# Schematic-DeepAmbiente.net
KiCad netlist of a schematic drawn in Altium Designer
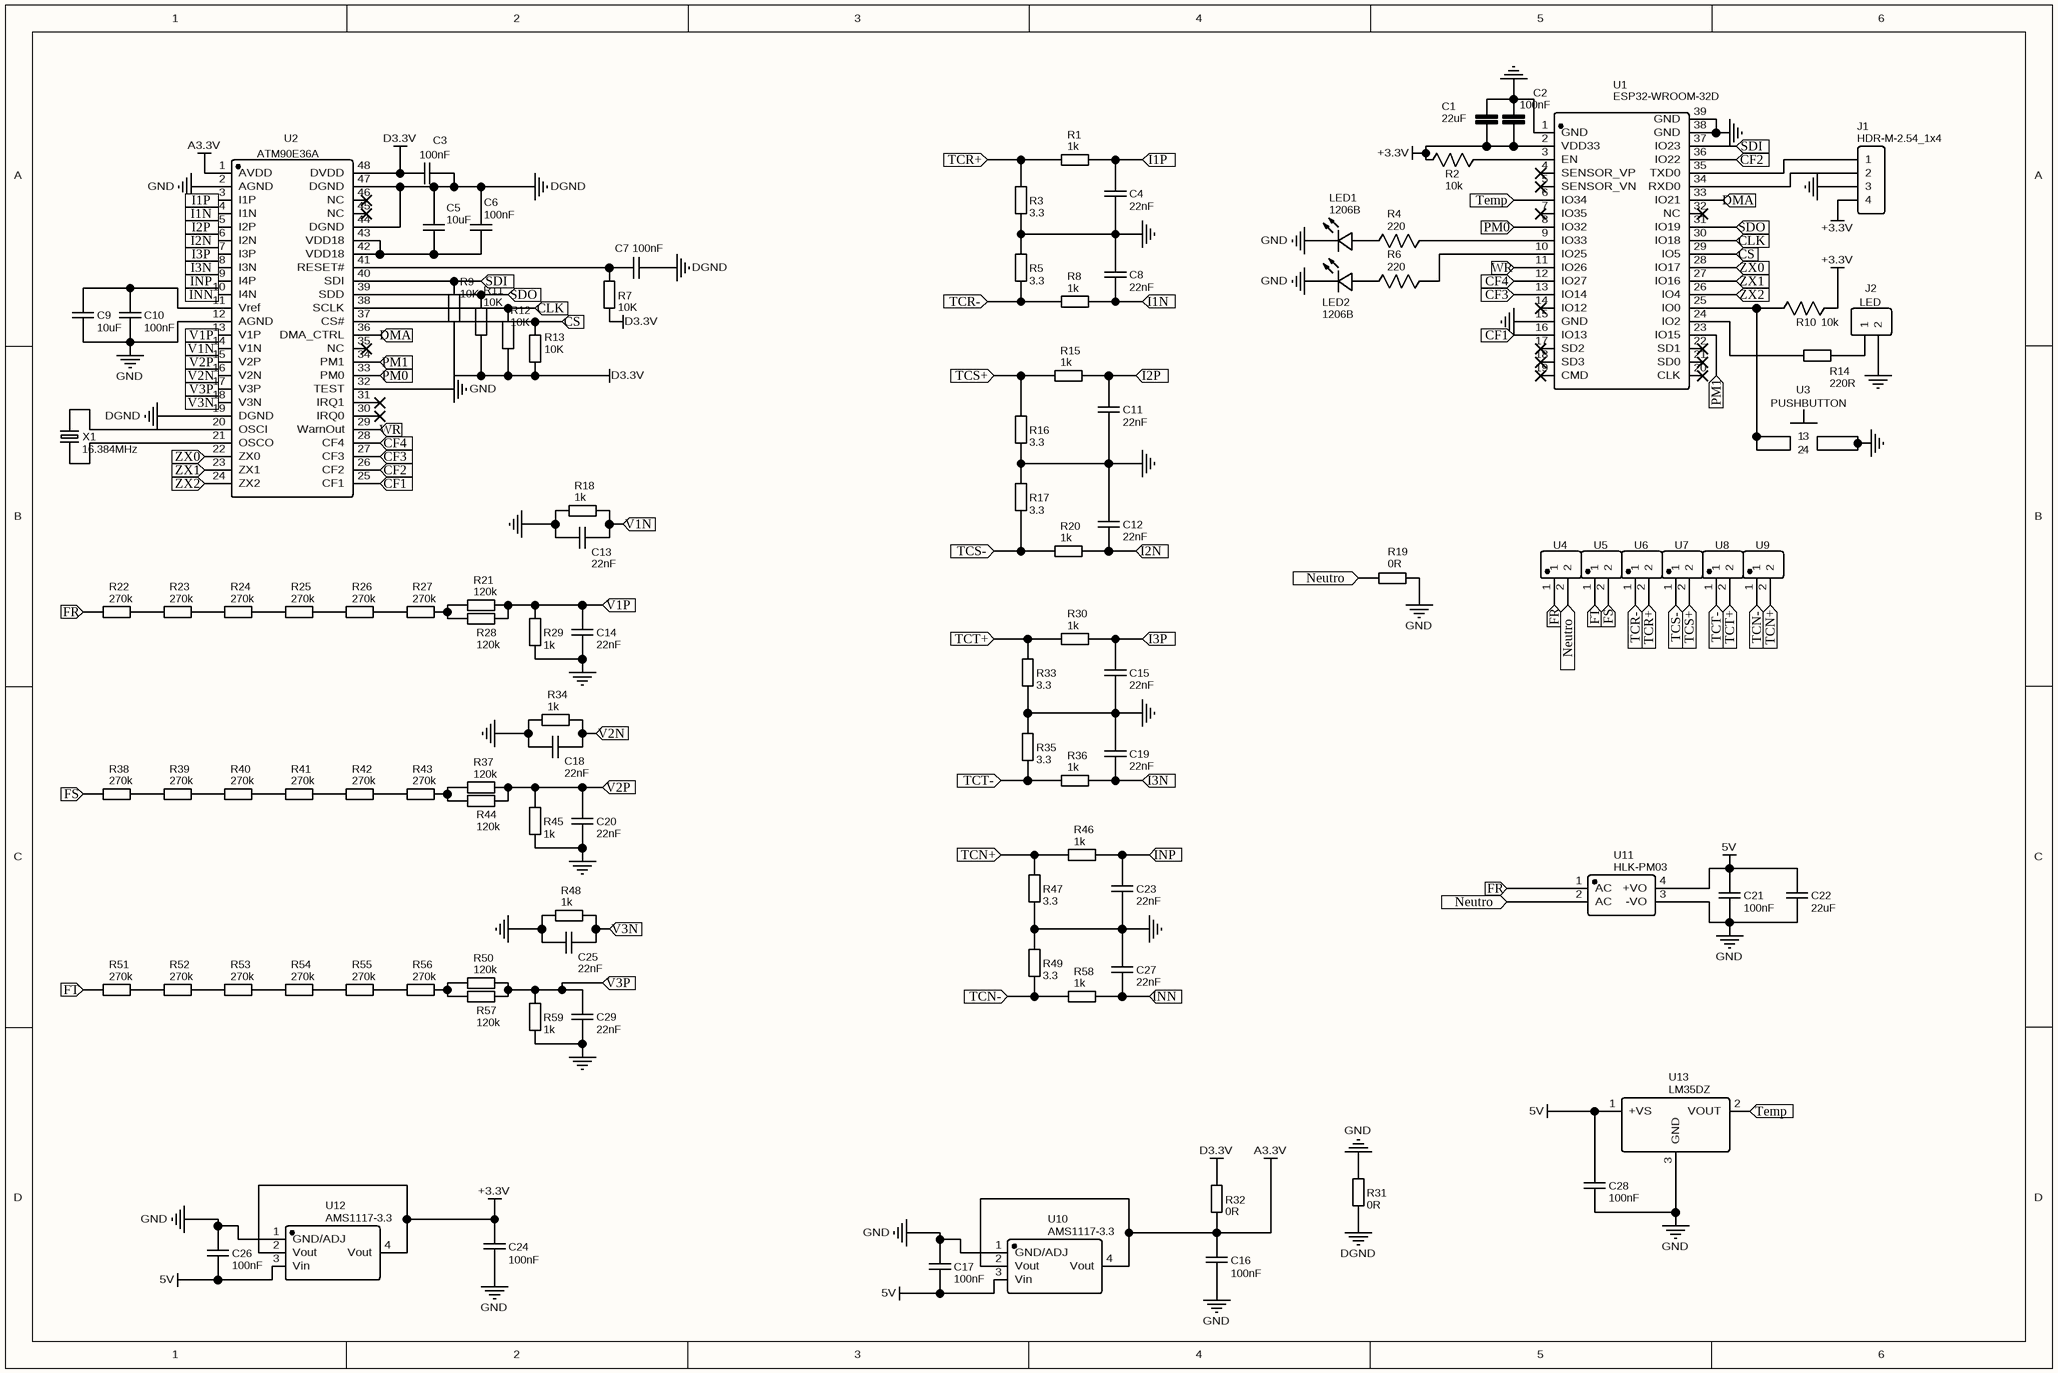
[diagram p0: Schematic-DeepAmbiente.schdoc]

(export (version "E")
  (design (tool "Eeschema 10.0.6"))
  (components
    (comp (ref "C1")
      (value "22uF")
      (description "Non-Polarized capacitor in various packages")
      (fields (field (name "CONTRIBUTOR") "DangerousPrototype"))
      (libsource (lib "altium-import") (part "root_0_22uF_"))
    )
    (comp (ref "C2")
      (value "100nF")
      (description "Non-Polarized capacitor in various packages")
      (fields (field (name "CONTRIBUTOR") "DangerousPrototype"))
      (libsource (lib "") (part "root_0_100nF__1"))
    )
    (comp (ref "C3")
      (value "100nF")
      (fields (field (name "CONTRIBUTOR") "Adisak Choochan"))
      (libsource (lib "altium-import") (part "root_3_100nF_"))
    )
    (comp (ref "C4")
      (value "22nF")
      (fields (field (name "CONTRIBUTOR") "Adisak Choochan"))
      (libsource (lib "altium-import") (part "root_0_22nF_"))
    )
    (comp (ref "C5")
      (value "10uF")
      (fields (field (name "CONTRIBUTOR") "Adisak Choochan"))
      (libsource (lib "altium-import") (part "root_0_10uF_"))
    )
    (comp (ref "C6")
      (value "100nF")
      (fields (field (name "CONTRIBUTOR") "Adisak Choochan"))
      (libsource (lib "altium-import") (part "root_0_100nF_"))
    )
    (comp (ref "C7")
      (value "100nF")
      (fields (field (name "CONTRIBUTOR") "Adisak Choochan"))
      (libsource (lib "altium-import") (part "root_1_100nF_"))
    )
    (comp (ref "C8")
      (value "22nF")
      (fields (field (name "CONTRIBUTOR") "Adisak Choochan"))
      (libsource (lib "altium-import") (part "root_0_22nF_"))
    )
    (comp (ref "C9")
      (value "10uF")
      (fields (field (name "CONTRIBUTOR") "Adisak Choochan"))
      (libsource (lib "altium-import") (part "root_0_10uF_"))
    )
    (comp (ref "C10")
      (value "100nF")
      (fields (field (name "CONTRIBUTOR") "Adisak Choochan"))
      (libsource (lib "altium-import") (part "root_0_100nF_"))
    )
    (comp (ref "C11")
      (value "22nF")
      (fields (field (name "CONTRIBUTOR") "Adisak Choochan"))
      (libsource (lib "altium-import") (part "root_0_22nF_"))
    )
    (comp (ref "C12")
      (value "22nF")
      (fields (field (name "CONTRIBUTOR") "Adisak Choochan"))
      (libsource (lib "altium-import") (part "root_0_22nF_"))
    )
    (comp (ref "C13")
      (value "22nF")
      (fields (field (name "CONTRIBUTOR") "Adisak Choochan"))
      (libsource (lib "altium-import") (part "root_1_22nF_"))
    )
    (comp (ref "C14")
      (value "22nF")
      (fields (field (name "CONTRIBUTOR") "Adisak Choochan"))
      (libsource (lib "altium-import") (part "root_0_22nF_"))
    )
    (comp (ref "C15")
      (value "22nF")
      (fields (field (name "CONTRIBUTOR") "Adisak Choochan"))
      (libsource (lib "altium-import") (part "root_0_22nF_"))
    )
    (comp (ref "C16")
      (value "100nF")
      (fields (field (name "CONTRIBUTOR") "Adisak Choochan"))
      (libsource (lib "altium-import") (part "root_2_100nF_"))
    )
    (comp (ref "C17")
      (value "100nF")
      (fields (field (name "CONTRIBUTOR") "Adisak Choochan"))
      (libsource (lib "altium-import") (part "root_2_100nF_"))
    )
    (comp (ref "C18")
      (value "22nF")
      (fields (field (name "CONTRIBUTOR") "Adisak Choochan"))
      (libsource (lib "altium-import") (part "root_1_22nF_"))
    )
    (comp (ref "C19")
      (value "22nF")
      (fields (field (name "CONTRIBUTOR") "Adisak Choochan"))
      (libsource (lib "altium-import") (part "root_0_22nF_"))
    )
    (comp (ref "C20")
      (value "22nF")
      (fields (field (name "CONTRIBUTOR") "Adisak Choochan"))
      (libsource (lib "altium-import") (part "root_0_22nF_"))
    )
    (comp (ref "C21")
      (value "100nF")
      (fields (field (name "CONTRIBUTOR") "Adisak Choochan"))
      (libsource (lib "altium-import") (part "root_0_100nF_"))
    )
    (comp (ref "C22")
      (value "22uF")
      (fields (field (name "CONTRIBUTOR") "Adisak Choochan"))
      (libsource (lib "") (part "root_0_22uF__1"))
    )
    (comp (ref "C23")
      (value "22nF")
      (fields (field (name "CONTRIBUTOR") "Adisak Choochan"))
      (libsource (lib "altium-import") (part "root_0_22nF_"))
    )
    (comp (ref "C24")
      (value "100nF")
      (fields (field (name "CONTRIBUTOR") "Adisak Choochan"))
      (libsource (lib "altium-import") (part "root_2_100nF_"))
    )
    (comp (ref "C25")
      (value "22nF")
      (fields (field (name "CONTRIBUTOR") "Adisak Choochan"))
      (libsource (lib "altium-import") (part "root_1_22nF_"))
    )
    (comp (ref "C26")
      (value "100nF")
      (fields (field (name "CONTRIBUTOR") "Adisak Choochan"))
      (libsource (lib "altium-import") (part "root_2_100nF_"))
    )
    (comp (ref "C27")
      (value "22nF")
      (fields (field (name "CONTRIBUTOR") "Adisak Choochan"))
      (libsource (lib "altium-import") (part "root_0_22nF_"))
    )
    (comp (ref "C28")
      (value "100nF")
      (fields (field (name "CONTRIBUTOR") "Adisak Choochan"))
      (libsource (lib "altium-import") (part "root_0_100nF_"))
    )
    (comp (ref "C29")
      (value "22nF")
      (fields (field (name "CONTRIBUTOR") "Adisak Choochan"))
      (libsource (lib "altium-import") (part "root_0_22nF_"))
    )
    (comp (ref "J1")
      (value "HDR-M-2.54_1x4")
      (fields (field (name "BOM_SUPPLIER PART") "C124378") (field (name "CONTRIBUTOR") "LCEDA_Lib"))
      (libsource (lib "altium-import") (part "root_0_HDR-M-2.54_1x4_"))
    )
    (comp (ref "J2")
      (value "LED")
      (fields (field (name "BOM_SUPPLIER PART") "C124375") (field (name "CONTRIBUTOR") "LCEDA_Lib"))
      (libsource (lib "altium-import") (part "root_1_LED_"))
    )
    (comp (ref "LED1")
      (value "1206B")
      (fields (field (name "BOM_SUPPLIER PART") "C72691"))
      (libsource (lib "altium-import") (part "root_0_1206B_"))
    )
    (comp (ref "LED2")
      (value "1206B")
      (fields (field (name "BOM_SUPPLIER PART") "C72691"))
      (libsource (lib "altium-import") (part "root_0_1206B_"))
    )
    (comp (ref "R1")
      (value "1k")
      (fields
        (field (name "BOM_SUPPLIER PART") "C267249")
        (field (name "BOM_MANUFACTURER PART") "R1206RXX302XJ04LTC")
        (field (name "CONTRIBUTOR") "LCSC")
      )
      (libsource (lib "altium-import") (part "root_2_1k_"))
    )
    (comp (ref "R2") (value "10k") (libsource (lib "altium-import") (part "root_0_10k_")))
    (comp (ref "R3")
      (value "3.3")
      (fields
        (field (name "BOM_SUPPLIER PART") "C267249")
        (field (name "BOM_MANUFACTURER PART") "R1206RXX302XJ04LTC")
        (field (name "CONTRIBUTOR") "LCSC")
      )
      (libsource (lib "altium-import") (part "root_1_3.3_"))
    )
    (comp (ref "R4") (value "220") (libsource (lib "altium-import") (part "root_0_220_")))
    (comp (ref "R5")
      (value "3.3")
      (fields
        (field (name "BOM_SUPPLIER PART") "C267249")
        (field (name "BOM_MANUFACTURER PART") "R1206RXX302XJ04LTC")
        (field (name "CONTRIBUTOR") "LCSC")
      )
      (libsource (lib "altium-import") (part "root_1_3.3_"))
    )
    (comp (ref "R6") (value "220") (libsource (lib "altium-import") (part "root_0_220_")))
    (comp (ref "R7")
      (value "10K")
      (fields
        (field (name "BOM_SUPPLIER PART") "C267249")
        (field (name "BOM_MANUFACTURER PART") "R1206RXX302XJ04LTC")
        (field (name "CONTRIBUTOR") "LCSC")
      )
      (libsource (lib "altium-import") (part "root_1_10K_"))
    )
    (comp (ref "R8")
      (value "1k")
      (fields
        (field (name "BOM_SUPPLIER PART") "C267249")
        (field (name "BOM_MANUFACTURER PART") "R1206RXX302XJ04LTC")
        (field (name "CONTRIBUTOR") "LCSC")
      )
      (libsource (lib "altium-import") (part "root_2_1k_"))
    )
    (comp (ref "R9")
      (value "10K")
      (fields
        (field (name "BOM_SUPPLIER PART") "C267249")
        (field (name "BOM_MANUFACTURER PART") "R1206RXX302XJ04LTC")
        (field (name "CONTRIBUTOR") "LCSC")
      )
      (libsource (lib "altium-import") (part "root_1_10K_"))
    )
    (comp (ref "R10") (value "10k") (libsource (lib "altium-import") (part "root_0_10k_")))
    (comp (ref "R11")
      (value "10K")
      (fields
        (field (name "BOM_SUPPLIER PART") "C267249")
        (field (name "BOM_MANUFACTURER PART") "R1206RXX302XJ04LTC")
        (field (name "CONTRIBUTOR") "LCSC")
      )
      (libsource (lib "altium-import") (part "root_1_10K_"))
    )
    (comp (ref "R12")
      (value "10K")
      (fields
        (field (name "BOM_SUPPLIER PART") "C267249")
        (field (name "BOM_MANUFACTURER PART") "R1206RXX302XJ04LTC")
        (field (name "CONTRIBUTOR") "LCSC")
      )
      (libsource (lib "altium-import") (part "root_1_10K_"))
    )
    (comp (ref "R13")
      (value "10K")
      (fields
        (field (name "BOM_SUPPLIER PART") "C267249")
        (field (name "BOM_MANUFACTURER PART") "R1206RXX302XJ04LTC")
        (field (name "CONTRIBUTOR") "LCSC")
      )
      (libsource (lib "altium-import") (part "root_1_10K_"))
    )
    (comp (ref "R14")
      (value "220R")
      (fields
        (field (name "BOM_SUPPLIER PART") "C267249")
        (field (name "BOM_MANUFACTURER PART") "R1206RXX302XJ04LTC")
        (field (name "CONTRIBUTOR") "LCSC")
      )
      (libsource (lib "altium-import") (part "root_2_220R_"))
    )
    (comp (ref "R15")
      (value "1k")
      (fields
        (field (name "BOM_SUPPLIER PART") "C267249")
        (field (name "BOM_MANUFACTURER PART") "R1206RXX302XJ04LTC")
        (field (name "CONTRIBUTOR") "LCSC")
      )
      (libsource (lib "altium-import") (part "root_2_1k_"))
    )
    (comp (ref "R16")
      (value "3.3")
      (fields
        (field (name "BOM_SUPPLIER PART") "C267249")
        (field (name "BOM_MANUFACTURER PART") "R1206RXX302XJ04LTC")
        (field (name "CONTRIBUTOR") "LCSC")
      )
      (libsource (lib "altium-import") (part "root_1_3.3_"))
    )
    (comp (ref "R17")
      (value "3.3")
      (fields
        (field (name "BOM_SUPPLIER PART") "C267249")
        (field (name "BOM_MANUFACTURER PART") "R1206RXX302XJ04LTC")
        (field (name "CONTRIBUTOR") "LCSC")
      )
      (libsource (lib "altium-import") (part "root_1_3.3_"))
    )
    (comp (ref "R18")
      (value "1k")
      (fields
        (field (name "BOM_SUPPLIER PART") "C267249")
        (field (name "BOM_MANUFACTURER PART") "R1206RXX302XJ04LTC")
        (field (name "CONTRIBUTOR") "LCSC")
      )
      (libsource (lib "altium-import") (part "root_2_1k_"))
    )
    (comp (ref "R19")
      (value "0R")
      (fields
        (field (name "BOM_SUPPLIER PART") "C267249")
        (field (name "BOM_MANUFACTURER PART") "R1206RXX302XJ04LTC")
        (field (name "CONTRIBUTOR") "LCSC")
      )
      (libsource (lib "altium-import") (part "root_0_0R_"))
    )
    (comp (ref "R20")
      (value "1k")
      (fields
        (field (name "BOM_SUPPLIER PART") "C267249")
        (field (name "BOM_MANUFACTURER PART") "R1206RXX302XJ04LTC")
        (field (name "CONTRIBUTOR") "LCSC")
      )
      (libsource (lib "altium-import") (part "root_2_1k_"))
    )
    (comp (ref "R21")
      (value "120k")
      (fields
        (field (name "BOM_SUPPLIER PART") "C267249")
        (field (name "BOM_MANUFACTURER PART") "R1206RXX302XJ04LTC")
        (field (name "CONTRIBUTOR") "LCSC")
      )
      (libsource (lib "altium-import") (part "root_2_120k_"))
    )
    (comp (ref "R22")
      (value "270k")
      (fields
        (field (name "BOM_SUPPLIER PART") "C267249")
        (field (name "BOM_MANUFACTURER PART") "R1206RXX302XJ04LTC")
        (field (name "CONTRIBUTOR") "LCSC")
      )
      (libsource (lib "altium-import") (part "root_2_270k_"))
    )
    (comp (ref "R23")
      (value "270k")
      (fields
        (field (name "BOM_SUPPLIER PART") "C267249")
        (field (name "BOM_MANUFACTURER PART") "R1206RXX302XJ04LTC")
        (field (name "CONTRIBUTOR") "LCSC")
      )
      (libsource (lib "altium-import") (part "root_2_270k_"))
    )
    (comp (ref "R24")
      (value "270k")
      (fields
        (field (name "BOM_SUPPLIER PART") "C267249")
        (field (name "BOM_MANUFACTURER PART") "R1206RXX302XJ04LTC")
        (field (name "CONTRIBUTOR") "LCSC")
      )
      (libsource (lib "altium-import") (part "root_2_270k_"))
    )
    (comp (ref "R25")
      (value "270k")
      (fields
        (field (name "BOM_SUPPLIER PART") "C267249")
        (field (name "BOM_MANUFACTURER PART") "R1206RXX302XJ04LTC")
        (field (name "CONTRIBUTOR") "LCSC")
      )
      (libsource (lib "altium-import") (part "root_2_270k_"))
    )
    (comp (ref "R26")
      (value "270k")
      (fields
        (field (name "BOM_SUPPLIER PART") "C267249")
        (field (name "BOM_MANUFACTURER PART") "R1206RXX302XJ04LTC")
        (field (name "CONTRIBUTOR") "LCSC")
      )
      (libsource (lib "altium-import") (part "root_2_270k_"))
    )
    (comp (ref "R27")
      (value "270k")
      (fields
        (field (name "BOM_SUPPLIER PART") "C267249")
        (field (name "BOM_MANUFACTURER PART") "R1206RXX302XJ04LTC")
        (field (name "CONTRIBUTOR") "LCSC")
      )
      (libsource (lib "altium-import") (part "root_2_270k_"))
    )
    (comp (ref "R28")
      (value "120k")
      (fields
        (field (name "BOM_SUPPLIER PART") "C267249")
        (field (name "BOM_MANUFACTURER PART") "R1206RXX302XJ04LTC")
        (field (name "CONTRIBUTOR") "LCSC")
      )
      (libsource (lib "altium-import") (part "root_2_120k_"))
    )
    (comp (ref "R29")
      (value "1k")
      (fields
        (field (name "BOM_SUPPLIER PART") "C267249")
        (field (name "BOM_MANUFACTURER PART") "R1206RXX302XJ04LTC")
        (field (name "CONTRIBUTOR") "LCSC")
      )
      (libsource (lib "altium-import") (part "root_3_1k_"))
    )
    (comp (ref "R30")
      (value "1k")
      (fields
        (field (name "BOM_SUPPLIER PART") "C267249")
        (field (name "BOM_MANUFACTURER PART") "R1206RXX302XJ04LTC")
        (field (name "CONTRIBUTOR") "LCSC")
      )
      (libsource (lib "altium-import") (part "root_2_1k_"))
    )
    (comp (ref "R31")
      (value "0R")
      (fields
        (field (name "BOM_SUPPLIER PART") "C267249")
        (field (name "BOM_MANUFACTURER PART") "R1206RXX302XJ04LTC")
        (field (name "CONTRIBUTOR") "LCSC")
      )
      (libsource (lib "altium-import") (part "root_1_0R_"))
    )
    (comp (ref "R32")
      (value "0R")
      (fields
        (field (name "BOM_SUPPLIER PART") "C267249")
        (field (name "BOM_MANUFACTURER PART") "R1206RXX302XJ04LTC")
        (field (name "CONTRIBUTOR") "LCSC")
      )
      (libsource (lib "altium-import") (part "root_1_0R_"))
    )
    (comp (ref "R33")
      (value "3.3")
      (fields
        (field (name "BOM_SUPPLIER PART") "C267249")
        (field (name "BOM_MANUFACTURER PART") "R1206RXX302XJ04LTC")
        (field (name "CONTRIBUTOR") "LCSC")
      )
      (libsource (lib "altium-import") (part "root_1_3.3_"))
    )
    (comp (ref "R34")
      (value "1k")
      (fields
        (field (name "BOM_SUPPLIER PART") "C267249")
        (field (name "BOM_MANUFACTURER PART") "R1206RXX302XJ04LTC")
        (field (name "CONTRIBUTOR") "LCSC")
      )
      (libsource (lib "altium-import") (part "root_2_1k_"))
    )
    (comp (ref "R35")
      (value "3.3")
      (fields
        (field (name "BOM_SUPPLIER PART") "C267249")
        (field (name "BOM_MANUFACTURER PART") "R1206RXX302XJ04LTC")
        (field (name "CONTRIBUTOR") "LCSC")
      )
      (libsource (lib "altium-import") (part "root_1_3.3_"))
    )
    (comp (ref "R36")
      (value "1k")
      (fields
        (field (name "BOM_SUPPLIER PART") "C267249")
        (field (name "BOM_MANUFACTURER PART") "R1206RXX302XJ04LTC")
        (field (name "CONTRIBUTOR") "LCSC")
      )
      (libsource (lib "altium-import") (part "root_2_1k_"))
    )
    (comp (ref "R37")
      (value "120k")
      (fields
        (field (name "BOM_SUPPLIER PART") "C267249")
        (field (name "BOM_MANUFACTURER PART") "R1206RXX302XJ04LTC")
        (field (name "CONTRIBUTOR") "LCSC")
      )
      (libsource (lib "altium-import") (part "root_2_120k_"))
    )
    (comp (ref "R38")
      (value "270k")
      (fields
        (field (name "BOM_SUPPLIER PART") "C267249")
        (field (name "BOM_MANUFACTURER PART") "R1206RXX302XJ04LTC")
        (field (name "CONTRIBUTOR") "LCSC")
      )
      (libsource (lib "altium-import") (part "root_2_270k_"))
    )
    (comp (ref "R39")
      (value "270k")
      (fields
        (field (name "BOM_SUPPLIER PART") "C267249")
        (field (name "BOM_MANUFACTURER PART") "R1206RXX302XJ04LTC")
        (field (name "CONTRIBUTOR") "LCSC")
      )
      (libsource (lib "altium-import") (part "root_2_270k_"))
    )
    (comp (ref "R40")
      (value "270k")
      (fields
        (field (name "BOM_SUPPLIER PART") "C267249")
        (field (name "BOM_MANUFACTURER PART") "R1206RXX302XJ04LTC")
        (field (name "CONTRIBUTOR") "LCSC")
      )
      (libsource (lib "altium-import") (part "root_2_270k_"))
    )
    (comp (ref "R41")
      (value "270k")
      (fields
        (field (name "BOM_SUPPLIER PART") "C267249")
        (field (name "BOM_MANUFACTURER PART") "R1206RXX302XJ04LTC")
        (field (name "CONTRIBUTOR") "LCSC")
      )
      (libsource (lib "altium-import") (part "root_2_270k_"))
    )
    (comp (ref "R42")
      (value "270k")
      (fields
        (field (name "BOM_SUPPLIER PART") "C267249")
        (field (name "BOM_MANUFACTURER PART") "R1206RXX302XJ04LTC")
        (field (name "CONTRIBUTOR") "LCSC")
      )
      (libsource (lib "altium-import") (part "root_2_270k_"))
    )
    (comp (ref "R43")
      (value "270k")
      (fields
        (field (name "BOM_SUPPLIER PART") "C267249")
        (field (name "BOM_MANUFACTURER PART") "R1206RXX302XJ04LTC")
        (field (name "CONTRIBUTOR") "LCSC")
      )
      (libsource (lib "altium-import") (part "root_2_270k_"))
    )
    (comp (ref "R44")
      (value "120k")
      (fields
        (field (name "BOM_SUPPLIER PART") "C267249")
        (field (name "BOM_MANUFACTURER PART") "R1206RXX302XJ04LTC")
        (field (name "CONTRIBUTOR") "LCSC")
      )
      (libsource (lib "altium-import") (part "root_2_120k_"))
    )
    (comp (ref "R45")
      (value "1k")
      (fields
        (field (name "BOM_SUPPLIER PART") "C267249")
        (field (name "BOM_MANUFACTURER PART") "R1206RXX302XJ04LTC")
        (field (name "CONTRIBUTOR") "LCSC")
      )
      (libsource (lib "altium-import") (part "root_3_1k_"))
    )
    (comp (ref "R46")
      (value "1k")
      (fields
        (field (name "BOM_SUPPLIER PART") "C267249")
        (field (name "BOM_MANUFACTURER PART") "R1206RXX302XJ04LTC")
        (field (name "CONTRIBUTOR") "LCSC")
      )
      (libsource (lib "altium-import") (part "root_2_1k_"))
    )
    (comp (ref "R47")
      (value "3.3")
      (fields
        (field (name "BOM_SUPPLIER PART") "C267249")
        (field (name "BOM_MANUFACTURER PART") "R1206RXX302XJ04LTC")
        (field (name "CONTRIBUTOR") "LCSC")
      )
      (libsource (lib "altium-import") (part "root_1_3.3_"))
    )
    (comp (ref "R48")
      (value "1k")
      (fields
        (field (name "BOM_SUPPLIER PART") "C267249")
        (field (name "BOM_MANUFACTURER PART") "R1206RXX302XJ04LTC")
        (field (name "CONTRIBUTOR") "LCSC")
      )
      (libsource (lib "altium-import") (part "root_2_1k_"))
    )
    (comp (ref "R49")
      (value "3.3")
      (fields
        (field (name "BOM_SUPPLIER PART") "C267249")
        (field (name "BOM_MANUFACTURER PART") "R1206RXX302XJ04LTC")
        (field (name "CONTRIBUTOR") "LCSC")
      )
      (libsource (lib "altium-import") (part "root_1_3.3_"))
    )
    (comp (ref "R50")
      (value "120k")
      (fields
        (field (name "BOM_SUPPLIER PART") "C267249")
        (field (name "BOM_MANUFACTURER PART") "R1206RXX302XJ04LTC")
        (field (name "CONTRIBUTOR") "LCSC")
      )
      (libsource (lib "altium-import") (part "root_2_120k_"))
    )
    (comp (ref "R51")
      (value "270k")
      (fields
        (field (name "BOM_SUPPLIER PART") "C267249")
        (field (name "BOM_MANUFACTURER PART") "R1206RXX302XJ04LTC")
        (field (name "CONTRIBUTOR") "LCSC")
      )
      (libsource (lib "altium-import") (part "root_2_270k_"))
    )
    (comp (ref "R52")
      (value "270k")
      (fields
        (field (name "BOM_SUPPLIER PART") "C267249")
        (field (name "BOM_MANUFACTURER PART") "R1206RXX302XJ04LTC")
        (field (name "CONTRIBUTOR") "LCSC")
      )
      (libsource (lib "altium-import") (part "root_2_270k_"))
    )
    (comp (ref "R53")
      (value "270k")
      (fields
        (field (name "BOM_SUPPLIER PART") "C267249")
        (field (name "BOM_MANUFACTURER PART") "R1206RXX302XJ04LTC")
        (field (name "CONTRIBUTOR") "LCSC")
      )
      (libsource (lib "altium-import") (part "root_2_270k_"))
    )
    (comp (ref "R54")
      (value "270k")
      (fields
        (field (name "BOM_SUPPLIER PART") "C267249")
        (field (name "BOM_MANUFACTURER PART") "R1206RXX302XJ04LTC")
        (field (name "CONTRIBUTOR") "LCSC")
      )
      (libsource (lib "altium-import") (part "root_2_270k_"))
    )
    (comp (ref "R55")
      (value "270k")
      (fields
        (field (name "BOM_SUPPLIER PART") "C267249")
        (field (name "BOM_MANUFACTURER PART") "R1206RXX302XJ04LTC")
        (field (name "CONTRIBUTOR") "LCSC")
      )
      (libsource (lib "altium-import") (part "root_2_270k_"))
    )
    (comp (ref "R56")
      (value "270k")
      (fields
        (field (name "BOM_SUPPLIER PART") "C267249")
        (field (name "BOM_MANUFACTURER PART") "R1206RXX302XJ04LTC")
        (field (name "CONTRIBUTOR") "LCSC")
      )
      (libsource (lib "altium-import") (part "root_2_270k_"))
    )
    (comp (ref "R57")
      (value "120k")
      (fields
        (field (name "BOM_SUPPLIER PART") "C267249")
        (field (name "BOM_MANUFACTURER PART") "R1206RXX302XJ04LTC")
        (field (name "CONTRIBUTOR") "LCSC")
      )
      (libsource (lib "altium-import") (part "root_2_120k_"))
    )
    (comp (ref "R58")
      (value "1k")
      (fields
        (field (name "BOM_SUPPLIER PART") "C267249")
        (field (name "BOM_MANUFACTURER PART") "R1206RXX302XJ04LTC")
        (field (name "CONTRIBUTOR") "LCSC")
      )
      (libsource (lib "altium-import") (part "root_2_1k_"))
    )
    (comp (ref "R59")
      (value "1k")
      (fields
        (field (name "BOM_SUPPLIER PART") "C267249")
        (field (name "BOM_MANUFACTURER PART") "R1206RXX302XJ04LTC")
        (field (name "CONTRIBUTOR") "LCSC")
      )
      (libsource (lib "altium-import") (part "root_3_1k_"))
    )
    (comp (ref "U1")
      (value "ESP32-WROOM-32D")
      (fields (field (name "BOM_SUPPLIER PART") "C473012") (field (name "CONTRIBUTOR") "LCSC"))
      (libsource (lib "altium-import") (part "root_0_ESP32-WROOM-32D_"))
    )
    (comp (ref "U2")
      (value "ATM90E36A")
      (fields
        (field (name "BOM_SUPPLIER PART") "C481363")
        (field (name "BOM_MANUFACTURER PART") "ATM90E36A-AU-R")
        (field (name "CONTRIBUTOR") "LCSC")
      )
      (libsource (lib "altium-import") (part "root_0_ATM90E36A_"))
    )
    (comp (ref "U3")
      (value "PUSHBUTTON")
      (fields (field (name "BOM_MANUFACTURER PART") "Pushbutton") (field (name "CONTRIBUTOR") "elnino"))
      (libsource (lib "altium-import") (part "root_0_PUSHBUTTON_"))
    )
    (comp (ref "U4")
      (value "KF301-5.0-2P")
      (fields (field (name "BOM_SUPPLIER PART") "C474881") (field (name "CONTRIBUTOR") "LCSC"))
      (libsource (lib "altium-import") (part "root_1_KF301-5.0-2P_"))
    )
    (comp (ref "U5")
      (value "KF301-5.0-2P")
      (fields (field (name "BOM_SUPPLIER PART") "C474881") (field (name "CONTRIBUTOR") "LCSC"))
      (libsource (lib "altium-import") (part "root_1_KF301-5.0-2P_"))
    )
    (comp (ref "U6")
      (value "KF301-5.0-2P")
      (fields (field (name "BOM_SUPPLIER PART") "C474881") (field (name "CONTRIBUTOR") "LCSC"))
      (libsource (lib "altium-import") (part "root_1_KF301-5.0-2P_"))
    )
    (comp (ref "U7")
      (value "KF301-5.0-2P")
      (fields (field (name "BOM_SUPPLIER PART") "C474881") (field (name "CONTRIBUTOR") "LCSC"))
      (libsource (lib "altium-import") (part "root_1_KF301-5.0-2P_"))
    )
    (comp (ref "U8")
      (value "KF301-5.0-2P")
      (fields (field (name "BOM_SUPPLIER PART") "C474881") (field (name "CONTRIBUTOR") "LCSC"))
      (libsource (lib "altium-import") (part "root_1_KF301-5.0-2P_"))
    )
    (comp (ref "U9")
      (value "KF301-5.0-2P")
      (fields (field (name "BOM_SUPPLIER PART") "C474881") (field (name "CONTRIBUTOR") "LCSC"))
      (libsource (lib "altium-import") (part "root_1_KF301-5.0-2P_"))
    )
    (comp (ref "U10")
      (value "AMS1117-3.3")
      (fields (field (name "BOM_SUPPLIER PART") "C6186"))
      (libsource (lib "altium-import") (part "root_0_AMS1117-3.3_"))
    )
    (comp (ref "U11")
      (value "HLK-PM03")
      (fields (field (name "BOM_SUPPLIER PART") "C209904") (field (name "CONTRIBUTOR") "LCSC"))
      (libsource (lib "altium-import") (part "root_0_HLK-PM03_"))
    )
    (comp (ref "U12")
      (value "AMS1117-3.3")
      (fields (field (name "BOM_SUPPLIER PART") "C6186"))
      (libsource (lib "altium-import") (part "root_0_AMS1117-3.3_"))
    )
    (comp (ref "U13")
      (value "LM35DZ")
      (fields (field (name "BOM_SUPPLIER PART") "C12165"))
      (libsource (lib "altium-import") (part "root_0_LM35DZ_"))
    )
    (comp (ref "X1")
      (value "16.384MHz")
      (fields
        (field (name "BOM_SUPPLIER PART") "C240932")
        (field (name "BOM_MANUFACTURER PART") "49S-16.384-20-20-20/A")
        (field (name "CONTRIBUTOR") "LCSC")
      )
      (libsource (lib "altium-import") (part "root_1_16.384MHz_"))
    )
  )
  (nets
    (net (code "1") (name "+3.3V") (class "Default")
      (node (ref "C1") (pin "2") (pinfunction "2_2") (pintype "passive"))
      (node (ref "C2") (pin "2") (pinfunction "2_2") (pintype "passive"))
      (node (ref "C24") (pin "1") (pinfunction "1_1") (pintype "passive"))
      (node (ref "J1") (pin "4") (pinfunction "4_4") (pintype "passive"))
      (node (ref "R10") (pin "2") (pinfunction "2_2") (pintype "passive"))
      (node (ref "R2") (pin "1") (pinfunction "1_1") (pintype "passive"))
      (node (ref "U1") (pin "2") (pinfunction "VDD33_2") (pintype "passive"))
      (node (ref "U12") (pin "2") (pinfunction "Vout_2") (pintype "passive"))
      (node (ref "U12") (pin "4") (pinfunction "Vout_4") (pintype "passive"))
    )
    (net (code "2") (name "/CF1") (class "Default")
      (node (ref "U1") (pin "16") (pinfunction "IO13_16") (pintype "passive"))
      (node (ref "U2") (pin "25") (pinfunction "CF1_25") (pintype "passive"))
    )
    (net (code "3") (name "/CF2") (class "Default")
      (node (ref "U1") (pin "36") (pinfunction "IO22_36") (pintype "passive"))
      (node (ref "U2") (pin "26") (pinfunction "CF2_26") (pintype "passive"))
    )
    (net (code "4") (name "/CF3") (class "Default")
      (node (ref "U1") (pin "13") (pinfunction "IO14_13") (pintype "passive"))
      (node (ref "U2") (pin "27") (pinfunction "CF3_27") (pintype "passive"))
    )
    (net (code "5") (name "/CF4") (class "Default")
      (node (ref "U1") (pin "12") (pinfunction "IO27_12") (pintype "passive"))
      (node (ref "U2") (pin "28") (pinfunction "CF4_28") (pintype "passive"))
    )
    (net (code "6") (name "/CLK") (class "Default")
      (node (ref "R12") (pin "2") (pinfunction "2_2") (pintype "passive"))
      (node (ref "U1") (pin "30") (pinfunction "IO18_30") (pintype "passive"))
      (node (ref "U2") (pin "38") (pinfunction "SCLK_38") (pintype "passive"))
    )
    (net (code "7") (name "/CS") (class "Default")
      (node (ref "R13") (pin "2") (pinfunction "2_2") (pintype "passive"))
      (node (ref "U1") (pin "29") (pinfunction "IO5_29") (pintype "passive"))
      (node (ref "U2") (pin "37") (pinfunction "CS#_37") (pintype "passive"))
    )
    (net (code "8") (name "/DMA") (class "Default")
      (node (ref "U1") (pin "33") (pinfunction "IO21_33") (pintype "passive"))
      (node (ref "U2") (pin "36") (pinfunction "DMA_CTRL_36") (pintype "passive"))
    )
    (net (code "9") (name "/FR") (class "Default")
      (node (ref "R22") (pin "2") (pinfunction "2_2") (pintype "passive"))
      (node (ref "U11") (pin "1") (pinfunction "AC_1") (pintype "passive"))
      (node (ref "U4") (pin "1") (pinfunction "1_1") (pintype "passive"))
    )
    (net (code "10") (name "/FS") (class "Default")
      (node (ref "R38") (pin "2") (pinfunction "2_2") (pintype "passive"))
      (node (ref "U5") (pin "2") (pinfunction "2_2") (pintype "passive"))
    )
    (net (code "11") (name "/FT") (class "Default")
      (node (ref "R51") (pin "2") (pinfunction "2_2") (pintype "passive"))
      (node (ref "U5") (pin "1") (pinfunction "1_1") (pintype "passive"))
    )
    (net (code "12") (name "/I1N") (class "Default")
      (node (ref "C8") (pin "1") (pinfunction "1_1") (pintype "passive"))
      (node (ref "R8") (pin "1") (pinfunction "1_1") (pintype "passive"))
      (node (ref "U2") (pin "4") (pinfunction "I1N_4") (pintype "passive"))
    )
    (net (code "13") (name "/I1P") (class "Default")
      (node (ref "C4") (pin "2") (pinfunction "2_2") (pintype "passive"))
      (node (ref "R1") (pin "1") (pinfunction "1_1") (pintype "passive"))
      (node (ref "U2") (pin "3") (pinfunction "I1P_3") (pintype "passive"))
    )
    (net (code "14") (name "/I2N") (class "Default")
      (node (ref "C12") (pin "1") (pinfunction "1_1") (pintype "passive"))
      (node (ref "R20") (pin "1") (pinfunction "1_1") (pintype "passive"))
      (node (ref "U2") (pin "6") (pinfunction "I2N_6") (pintype "passive"))
    )
    (net (code "15") (name "/I2P") (class "Default")
      (node (ref "C11") (pin "2") (pinfunction "2_2") (pintype "passive"))
      (node (ref "R15") (pin "1") (pinfunction "1_1") (pintype "passive"))
      (node (ref "U2") (pin "5") (pinfunction "I2P_5") (pintype "passive"))
    )
    (net (code "16") (name "/I3N") (class "Default")
      (node (ref "C19") (pin "1") (pinfunction "1_1") (pintype "passive"))
      (node (ref "R36") (pin "1") (pinfunction "1_1") (pintype "passive"))
      (node (ref "U2") (pin "8") (pinfunction "I3N_8") (pintype "passive"))
    )
    (net (code "17") (name "/I3P") (class "Default")
      (node (ref "C15") (pin "2") (pinfunction "2_2") (pintype "passive"))
      (node (ref "R30") (pin "1") (pinfunction "1_1") (pintype "passive"))
      (node (ref "U2") (pin "7") (pinfunction "I3P_7") (pintype "passive"))
    )
    (net (code "18") (name "/INN") (class "Default")
      (node (ref "C27") (pin "1") (pinfunction "1_1") (pintype "passive"))
      (node (ref "R58") (pin "1") (pinfunction "1_1") (pintype "passive"))
      (node (ref "U2") (pin "10") (pinfunction "I4N_10") (pintype "passive"))
    )
    (net (code "19") (name "/INP") (class "Default")
      (node (ref "C23") (pin "2") (pinfunction "2_2") (pintype "passive"))
      (node (ref "R46") (pin "1") (pinfunction "1_1") (pintype "passive"))
      (node (ref "U2") (pin "9") (pinfunction "I4P_9") (pintype "passive"))
    )
    (net (code "20") (name "/Neutro") (class "Default")
      (node (ref "R19") (pin "1") (pinfunction "1_1") (pintype "passive"))
      (node (ref "U11") (pin "2") (pinfunction "AC_2") (pintype "passive"))
      (node (ref "U4") (pin "2") (pinfunction "2_2") (pintype "passive"))
    )
    (net (code "21") (name "/PM0") (class "Default")
      (node (ref "U1") (pin "8") (pinfunction "IO32_8") (pintype "passive"))
      (node (ref "U2") (pin "33") (pinfunction "PM0_33") (pintype "passive"))
    )
    (net (code "22") (name "/PM1") (class "Default")
      (node (ref "U1") (pin "23") (pinfunction "IO15_23") (pintype "passive"))
      (node (ref "U2") (pin "34") (pinfunction "PM1_34") (pintype "passive"))
    )
    (net (code "23") (name "/SDI") (class "Default")
      (node (ref "R9") (pin "2") (pinfunction "2_2") (pintype "passive"))
      (node (ref "U1") (pin "37") (pinfunction "IO23_37") (pintype "passive"))
      (node (ref "U2") (pin "40") (pinfunction "SDI_40") (pintype "passive"))
    )
    (net (code "24") (name "/SDO") (class "Default")
      (node (ref "R11") (pin "2") (pinfunction "2_2") (pintype "passive"))
      (node (ref "U1") (pin "31") (pinfunction "IO19_31") (pintype "passive"))
      (node (ref "U2") (pin "39") (pinfunction "SDD_39") (pintype "passive"))
    )
    (net (code "25") (name "/TCN+") (class "Default")
      (node (ref "R46") (pin "2") (pinfunction "2_2") (pintype "passive"))
      (node (ref "R47") (pin "2") (pinfunction "2_2") (pintype "passive"))
      (node (ref "U9") (pin "2") (pinfunction "2_2") (pintype "passive"))
    )
    (net (code "26") (name "/TCN-") (class "Default")
      (node (ref "R49") (pin "1") (pinfunction "1_1") (pintype "passive"))
      (node (ref "R58") (pin "2") (pinfunction "2_2") (pintype "passive"))
      (node (ref "U9") (pin "1") (pinfunction "1_1") (pintype "passive"))
    )
    (net (code "27") (name "/TCR+") (class "Default")
      (node (ref "R1") (pin "2") (pinfunction "2_2") (pintype "passive"))
      (node (ref "R3") (pin "2") (pinfunction "2_2") (pintype "passive"))
      (node (ref "U6") (pin "2") (pinfunction "2_2") (pintype "passive"))
    )
    (net (code "28") (name "/TCR-") (class "Default")
      (node (ref "R5") (pin "1") (pinfunction "1_1") (pintype "passive"))
      (node (ref "R8") (pin "2") (pinfunction "2_2") (pintype "passive"))
      (node (ref "U6") (pin "1") (pinfunction "1_1") (pintype "passive"))
    )
    (net (code "29") (name "/TCS+") (class "Default")
      (node (ref "R15") (pin "2") (pinfunction "2_2") (pintype "passive"))
      (node (ref "R16") (pin "2") (pinfunction "2_2") (pintype "passive"))
      (node (ref "U7") (pin "2") (pinfunction "2_2") (pintype "passive"))
    )
    (net (code "30") (name "/TCS-") (class "Default")
      (node (ref "R17") (pin "1") (pinfunction "1_1") (pintype "passive"))
      (node (ref "R20") (pin "2") (pinfunction "2_2") (pintype "passive"))
      (node (ref "U7") (pin "1") (pinfunction "1_1") (pintype "passive"))
    )
    (net (code "31") (name "/TCT+") (class "Default")
      (node (ref "R30") (pin "2") (pinfunction "2_2") (pintype "passive"))
      (node (ref "R33") (pin "2") (pinfunction "2_2") (pintype "passive"))
      (node (ref "U8") (pin "2") (pinfunction "2_2") (pintype "passive"))
    )
    (net (code "32") (name "/TCT-") (class "Default")
      (node (ref "R35") (pin "1") (pinfunction "1_1") (pintype "passive"))
      (node (ref "R36") (pin "2") (pinfunction "2_2") (pintype "passive"))
      (node (ref "U8") (pin "1") (pinfunction "1_1") (pintype "passive"))
    )
    (net (code "33") (name "/Temp") (class "Default")
      (node (ref "U1") (pin "6") (pinfunction "IO34_6") (pintype "passive"))
      (node (ref "U13") (pin "2") (pinfunction "VOUT_2") (pintype "passive"))
    )
    (net (code "34") (name "/V1N") (class "Default")
      (node (ref "C13") (pin "1") (pinfunction "1_1") (pintype "passive"))
      (node (ref "R18") (pin "1") (pinfunction "1_1") (pintype "passive"))
      (node (ref "U2") (pin "14") (pinfunction "V1N_14") (pintype "passive"))
    )
    (net (code "35") (name "/V1P") (class "Default")
      (node (ref "C14") (pin "2") (pinfunction "2_2") (pintype "passive"))
      (node (ref "R21") (pin "1") (pinfunction "1_1") (pintype "passive"))
      (node (ref "R28") (pin "1") (pinfunction "1_1") (pintype "passive"))
      (node (ref "R29") (pin "1") (pinfunction "1_1") (pintype "passive"))
      (node (ref "U2") (pin "13") (pinfunction "V1P_13") (pintype "passive"))
    )
    (net (code "36") (name "/V2N") (class "Default")
      (node (ref "C18") (pin "1") (pinfunction "1_1") (pintype "passive"))
      (node (ref "R34") (pin "1") (pinfunction "1_1") (pintype "passive"))
      (node (ref "U2") (pin "16") (pinfunction "V2N_16") (pintype "passive"))
    )
    (net (code "37") (name "/V2P") (class "Default")
      (node (ref "C20") (pin "2") (pinfunction "2_2") (pintype "passive"))
      (node (ref "R37") (pin "1") (pinfunction "1_1") (pintype "passive"))
      (node (ref "R44") (pin "1") (pinfunction "1_1") (pintype "passive"))
      (node (ref "R45") (pin "1") (pinfunction "1_1") (pintype "passive"))
      (node (ref "U2") (pin "15") (pinfunction "V2P_15") (pintype "passive"))
    )
    (net (code "38") (name "/V3N") (class "Default")
      (node (ref "C25") (pin "1") (pinfunction "1_1") (pintype "passive"))
      (node (ref "R48") (pin "1") (pinfunction "1_1") (pintype "passive"))
      (node (ref "U2") (pin "18") (pinfunction "V3N_18") (pintype "passive"))
    )
    (net (code "39") (name "/V3P") (class "Default")
      (node (ref "C29") (pin "2") (pinfunction "2_2") (pintype "passive"))
      (node (ref "R50") (pin "1") (pinfunction "1_1") (pintype "passive"))
      (node (ref "R57") (pin "1") (pinfunction "1_1") (pintype "passive"))
      (node (ref "R59") (pin "1") (pinfunction "1_1") (pintype "passive"))
      (node (ref "U2") (pin "17") (pinfunction "V3P_17") (pintype "passive"))
    )
    (net (code "40") (name "/WR") (class "Default")
      (node (ref "U1") (pin "11") (pinfunction "IO26_11") (pintype "passive"))
      (node (ref "U2") (pin "29") (pinfunction "WarnOut_29") (pintype "passive"))
    )
    (net (code "41") (name "/ZX0") (class "Default")
      (node (ref "U1") (pin "28") (pinfunction "IO17_28") (pintype "passive"))
      (node (ref "U2") (pin "22") (pinfunction "ZX0_22") (pintype "passive"))
    )
    (net (code "42") (name "/ZX1") (class "Default")
      (node (ref "U1") (pin "27") (pinfunction "IO16_27") (pintype "passive"))
      (node (ref "U2") (pin "23") (pinfunction "ZX1_23") (pintype "passive"))
    )
    (net (code "43") (name "/ZX2") (class "Default")
      (node (ref "U1") (pin "26") (pinfunction "IO4_26") (pintype "passive"))
      (node (ref "U2") (pin "24") (pinfunction "ZX2_24") (pintype "passive"))
    )
    (net (code "44") (name "5V") (class "Default")
      (node (ref "C17") (pin "2") (pinfunction "2_2") (pintype "passive"))
      (node (ref "C21") (pin "2") (pinfunction "2_2") (pintype "passive"))
      (node (ref "C22") (pin "2") (pinfunction "2_2") (pintype "passive"))
      (node (ref "C26") (pin "2") (pinfunction "2_2") (pintype "passive"))
      (node (ref "C28") (pin "2") (pinfunction "2_2") (pintype "passive"))
      (node (ref "U10") (pin "3") (pinfunction "Vin_3") (pintype "passive"))
      (node (ref "U11") (pin "4") (pinfunction "+VO_4") (pintype "passive"))
      (node (ref "U12") (pin "3") (pinfunction "Vin_3") (pintype "passive"))
      (node (ref "U13") (pin "1") (pinfunction "+VS_1") (pintype "passive"))
    )
    (net (code "45") (name "A3.3V") (class "Default")
      (node (ref "C16") (pin "1") (pinfunction "1_1") (pintype "passive"))
      (node (ref "R32") (pin "1") (pinfunction "1_1") (pintype "passive"))
      (node (ref "U10") (pin "2") (pinfunction "Vout_2") (pintype "passive"))
      (node (ref "U10") (pin "4") (pinfunction "Vout_4") (pintype "passive"))
      (node (ref "U2") (pin "1") (pinfunction "AVDD_1") (pintype "passive"))
    )
    (net (code "46") (name "D3.3V") (class "Default")
      (node (ref "C3") (pin "1") (pinfunction "1_1") (pintype "passive"))
      (node (ref "R11") (pin "1") (pinfunction "1_1") (pintype "passive"))
      (node (ref "R12") (pin "1") (pinfunction "1_1") (pintype "passive"))
      (node (ref "R13") (pin "1") (pinfunction "1_1") (pintype "passive"))
      (node (ref "R32") (pin "2") (pinfunction "2_2") (pintype "passive"))
      (node (ref "R7") (pin "1") (pinfunction "1_1") (pintype "passive"))
      (node (ref "R9") (pin "1") (pinfunction "1_1") (pintype "passive"))
      (node (ref "U2") (pin "48") (pinfunction "DVDD_48") (pintype "passive"))
    )
    (net (code "47") (name "DGND") (class "Default")
      (node (ref "C3") (pin "2") (pinfunction "2_2") (pintype "passive"))
      (node (ref "C5") (pin "2") (pinfunction "2_2") (pintype "passive"))
      (node (ref "C6") (pin "2") (pinfunction "2_2") (pintype "passive"))
      (node (ref "C7") (pin "1") (pinfunction "1_1") (pintype "passive"))
      (node (ref "R31") (pin "1") (pinfunction "1_1") (pintype "passive"))
      (node (ref "U2") (pin "19") (pinfunction "DGND_19") (pintype "passive"))
      (node (ref "U2") (pin "44") (pinfunction "DGND_44") (pintype "passive"))
      (node (ref "U2") (pin "47") (pinfunction "DGND_47") (pintype "passive"))
    )
    (net (code "48") (name "GND") (class "Default")
      (node (ref "C1") (pin "1") (pinfunction "1_1") (pintype "passive"))
      (node (ref "C10") (pin "1") (pinfunction "1_1") (pintype "passive"))
      (node (ref "C11") (pin "1") (pinfunction "1_1") (pintype "passive"))
      (node (ref "C12") (pin "2") (pinfunction "2_2") (pintype "passive"))
      (node (ref "C13") (pin "2") (pinfunction "2_2") (pintype "passive"))
      (node (ref "C14") (pin "1") (pinfunction "1_1") (pintype "passive"))
      (node (ref "C15") (pin "1") (pinfunction "1_1") (pintype "passive"))
      (node (ref "C16") (pin "2") (pinfunction "2_2") (pintype "passive"))
      (node (ref "C17") (pin "1") (pinfunction "1_1") (pintype "passive"))
      (node (ref "C18") (pin "2") (pinfunction "2_2") (pintype "passive"))
      (node (ref "C19") (pin "2") (pinfunction "2_2") (pintype "passive"))
      (node (ref "C2") (pin "1") (pinfunction "1_1") (pintype "passive"))
      (node (ref "C20") (pin "1") (pinfunction "1_1") (pintype "passive"))
      (node (ref "C21") (pin "1") (pinfunction "1_1") (pintype "passive"))
      (node (ref "C22") (pin "1") (pinfunction "1_1") (pintype "passive"))
      (node (ref "C23") (pin "1") (pinfunction "1_1") (pintype "passive"))
      (node (ref "C24") (pin "2") (pinfunction "2_2") (pintype "passive"))
      (node (ref "C25") (pin "2") (pinfunction "2_2") (pintype "passive"))
      (node (ref "C26") (pin "1") (pinfunction "1_1") (pintype "passive"))
      (node (ref "C27") (pin "2") (pinfunction "2_2") (pintype "passive"))
      (node (ref "C28") (pin "1") (pinfunction "1_1") (pintype "passive"))
      (node (ref "C29") (pin "1") (pinfunction "1_1") (pintype "passive"))
      (node (ref "C4") (pin "1") (pinfunction "1_1") (pintype "passive"))
      (node (ref "C8") (pin "2") (pinfunction "2_2") (pintype "passive"))
      (node (ref "C9") (pin "1") (pinfunction "1_1") (pintype "passive"))
      (node (ref "J1") (pin "3") (pinfunction "3_3") (pintype "passive"))
      (node (ref "J2") (pin "2") (pinfunction "2_2") (pintype "passive"))
      (node (ref "LED1") (pin "2") (pinfunction "2_2") (pintype "passive"))
      (node (ref "LED2") (pin "2") (pinfunction "2_2") (pintype "passive"))
      (node (ref "R16") (pin "1") (pinfunction "1_1") (pintype "passive"))
      (node (ref "R17") (pin "2") (pinfunction "2_2") (pintype "passive"))
      (node (ref "R18") (pin "2") (pinfunction "2_2") (pintype "passive"))
      (node (ref "R19") (pin "2") (pinfunction "2_2") (pintype "passive"))
      (node (ref "R29") (pin "2") (pinfunction "2_2") (pintype "passive"))
      (node (ref "R3") (pin "1") (pinfunction "1_1") (pintype "passive"))
      (node (ref "R31") (pin "2") (pinfunction "2_2") (pintype "passive"))
      (node (ref "R33") (pin "1") (pinfunction "1_1") (pintype "passive"))
      (node (ref "R34") (pin "2") (pinfunction "2_2") (pintype "passive"))
      (node (ref "R35") (pin "2") (pinfunction "2_2") (pintype "passive"))
      (node (ref "R45") (pin "2") (pinfunction "2_2") (pintype "passive"))
      (node (ref "R47") (pin "1") (pinfunction "1_1") (pintype "passive"))
      (node (ref "R48") (pin "2") (pinfunction "2_2") (pintype "passive"))
      (node (ref "R49") (pin "2") (pinfunction "2_2") (pintype "passive"))
      (node (ref "R5") (pin "2") (pinfunction "2_2") (pintype "passive"))
      (node (ref "R59") (pin "2") (pinfunction "2_2") (pintype "passive"))
      (node (ref "U1") (pin "1") (pinfunction "GND_1") (pintype "passive"))
      (node (ref "U1") (pin "15") (pinfunction "GND_15") (pintype "passive"))
      (node (ref "U1") (pin "38") (pinfunction "GND_38") (pintype "passive"))
      (node (ref "U1") (pin "39") (pinfunction "GND_39") (pintype "passive"))
      (node (ref "U10") (pin "1") (pinfunction "GND/ADJ_1") (pintype "passive"))
      (node (ref "U11") (pin "3") (pinfunction "-VO_3") (pintype "passive"))
      (node (ref "U12") (pin "1") (pinfunction "GND/ADJ_1") (pintype "passive"))
      (node (ref "U13") (pin "3") (pinfunction "GND_3") (pintype "passive"))
      (node (ref "U2") (pin "12") (pinfunction "AGND_12") (pintype "passive"))
      (node (ref "U2") (pin "2") (pinfunction "AGND_2") (pintype "passive"))
      (node (ref "U2") (pin "32") (pinfunction "TEST_32") (pintype "passive"))
      (node (ref "U3") (pin "3") (pinfunction "3_3") (pintype "passive"))
      (node (ref "U3") (pin "4") (pinfunction "4_4") (pintype "passive"))
    )
    (net (code "49") (name "Net-(C5-Pad1)") (class "Default")
      (node (ref "C5") (pin "1") (pinfunction "1_1") (pintype "passive"))
      (node (ref "C6") (pin "1") (pinfunction "1_1") (pintype "passive"))
      (node (ref "U2") (pin "42") (pinfunction "VDD18_42") (pintype "passive"))
      (node (ref "U2") (pin "43") (pinfunction "VDD18_43") (pintype "passive"))
    )
    (net (code "50") (name "Net-(J2-Pad1)") (class "Default")
      (node (ref "J2") (pin "1") (pinfunction "1_1") (pintype "passive"))
      (node (ref "R14") (pin "1") (pinfunction "1_1") (pintype "passive"))
    )
    (net (code "51") (name "Net-(LED1-Pad1)") (class "Default")
      (node (ref "LED1") (pin "1") (pinfunction "1_1") (pintype "passive"))
      (node (ref "R4") (pin "1") (pinfunction "1_1") (pintype "passive"))
    )
    (net (code "52") (name "Net-(LED2-Pad1)") (class "Default")
      (node (ref "LED2") (pin "1") (pinfunction "1_1") (pintype "passive"))
      (node (ref "R6") (pin "1") (pinfunction "1_1") (pintype "passive"))
    )
    (net (code "53") (name "Net-(R21-Pad2)") (class "Default")
      (node (ref "R21") (pin "2") (pinfunction "2_2") (pintype "passive"))
      (node (ref "R27") (pin "1") (pinfunction "1_1") (pintype "passive"))
      (node (ref "R28") (pin "2") (pinfunction "2_2") (pintype "passive"))
    )
    (net (code "54") (name "Net-(R22-Pad1)") (class "Default")
      (node (ref "R22") (pin "1") (pinfunction "1_1") (pintype "passive"))
      (node (ref "R23") (pin "2") (pinfunction "2_2") (pintype "passive"))
    )
    (net (code "55") (name "Net-(R23-Pad1)") (class "Default")
      (node (ref "R23") (pin "1") (pinfunction "1_1") (pintype "passive"))
      (node (ref "R24") (pin "2") (pinfunction "2_2") (pintype "passive"))
    )
    (net (code "56") (name "Net-(R24-Pad1)") (class "Default")
      (node (ref "R24") (pin "1") (pinfunction "1_1") (pintype "passive"))
      (node (ref "R25") (pin "2") (pinfunction "2_2") (pintype "passive"))
    )
    (net (code "57") (name "Net-(R25-Pad1)") (class "Default")
      (node (ref "R25") (pin "1") (pinfunction "1_1") (pintype "passive"))
      (node (ref "R26") (pin "2") (pinfunction "2_2") (pintype "passive"))
    )
    (net (code "58") (name "Net-(R26-Pad1)") (class "Default")
      (node (ref "R26") (pin "1") (pinfunction "1_1") (pintype "passive"))
      (node (ref "R27") (pin "2") (pinfunction "2_2") (pintype "passive"))
    )
    (net (code "59") (name "Net-(R37-Pad2)") (class "Default")
      (node (ref "R37") (pin "2") (pinfunction "2_2") (pintype "passive"))
      (node (ref "R43") (pin "1") (pinfunction "1_1") (pintype "passive"))
      (node (ref "R44") (pin "2") (pinfunction "2_2") (pintype "passive"))
    )
    (net (code "60") (name "Net-(R38-Pad1)") (class "Default")
      (node (ref "R38") (pin "1") (pinfunction "1_1") (pintype "passive"))
      (node (ref "R39") (pin "2") (pinfunction "2_2") (pintype "passive"))
    )
    (net (code "61") (name "Net-(R39-Pad1)") (class "Default")
      (node (ref "R39") (pin "1") (pinfunction "1_1") (pintype "passive"))
      (node (ref "R40") (pin "2") (pinfunction "2_2") (pintype "passive"))
    )
    (net (code "62") (name "Net-(R40-Pad1)") (class "Default")
      (node (ref "R40") (pin "1") (pinfunction "1_1") (pintype "passive"))
      (node (ref "R41") (pin "2") (pinfunction "2_2") (pintype "passive"))
    )
    (net (code "63") (name "Net-(R41-Pad1)") (class "Default")
      (node (ref "R41") (pin "1") (pinfunction "1_1") (pintype "passive"))
      (node (ref "R42") (pin "2") (pinfunction "2_2") (pintype "passive"))
    )
    (net (code "64") (name "Net-(R42-Pad1)") (class "Default")
      (node (ref "R42") (pin "1") (pinfunction "1_1") (pintype "passive"))
      (node (ref "R43") (pin "2") (pinfunction "2_2") (pintype "passive"))
    )
    (net (code "65") (name "Net-(R50-Pad2)") (class "Default")
      (node (ref "R50") (pin "2") (pinfunction "2_2") (pintype "passive"))
      (node (ref "R56") (pin "1") (pinfunction "1_1") (pintype "passive"))
      (node (ref "R57") (pin "2") (pinfunction "2_2") (pintype "passive"))
    )
    (net (code "66") (name "Net-(R51-Pad1)") (class "Default")
      (node (ref "R51") (pin "1") (pinfunction "1_1") (pintype "passive"))
      (node (ref "R52") (pin "2") (pinfunction "2_2") (pintype "passive"))
    )
    (net (code "67") (name "Net-(R52-Pad1)") (class "Default")
      (node (ref "R52") (pin "1") (pinfunction "1_1") (pintype "passive"))
      (node (ref "R53") (pin "2") (pinfunction "2_2") (pintype "passive"))
    )
    (net (code "68") (name "Net-(R53-Pad1)") (class "Default")
      (node (ref "R53") (pin "1") (pinfunction "1_1") (pintype "passive"))
      (node (ref "R54") (pin "2") (pinfunction "2_2") (pintype "passive"))
    )
    (net (code "69") (name "Net-(R54-Pad1)") (class "Default")
      (node (ref "R54") (pin "1") (pinfunction "1_1") (pintype "passive"))
      (node (ref "R55") (pin "2") (pinfunction "2_2") (pintype "passive"))
    )
    (net (code "70") (name "Net-(R55-Pad1)") (class "Default")
      (node (ref "R55") (pin "1") (pinfunction "1_1") (pintype "passive"))
      (node (ref "R56") (pin "2") (pinfunction "2_2") (pintype "passive"))
    )
    (net (code "71") (name "Net-(U1-EN)") (class "Default")
      (node (ref "R2") (pin "2") (pinfunction "2_2") (pintype "passive"))
      (node (ref "U1") (pin "3") (pinfunction "EN_3") (pintype "passive"))
    )
    (net (code "72") (name "Net-(U1-IO0)") (class "Default")
      (node (ref "R10") (pin "1") (pinfunction "1_1") (pintype "passive"))
      (node (ref "U1") (pin "25") (pinfunction "IO0_25") (pintype "passive"))
      (node (ref "U3") (pin "1") (pinfunction "1_1") (pintype "passive"))
      (node (ref "U3") (pin "2") (pinfunction "2_2") (pintype "passive"))
    )
    (net (code "73") (name "Net-(U1-IO2)") (class "Default")
      (node (ref "R14") (pin "2") (pinfunction "2_2") (pintype "passive"))
      (node (ref "U1") (pin "24") (pinfunction "IO2_24") (pintype "passive"))
    )
    (net (code "74") (name "Net-(U1-IO25)") (class "Default")
      (node (ref "R6") (pin "2") (pinfunction "2_2") (pintype "passive"))
      (node (ref "U1") (pin "10") (pinfunction "IO25_10") (pintype "passive"))
    )
    (net (code "75") (name "Net-(U1-IO33)") (class "Default")
      (node (ref "R4") (pin "2") (pinfunction "2_2") (pintype "passive"))
      (node (ref "U1") (pin "9") (pinfunction "IO33_9") (pintype "passive"))
    )
    (net (code "76") (name "Net-(U1-RXD0)") (class "Default")
      (node (ref "J1") (pin "2") (pinfunction "2_2") (pintype "passive"))
      (node (ref "U1") (pin "34") (pinfunction "RXD0_34") (pintype "passive"))
    )
    (net (code "77") (name "Net-(U1-TXD0)") (class "Default")
      (node (ref "J1") (pin "1") (pinfunction "1_1") (pintype "passive"))
      (node (ref "U1") (pin "35") (pinfunction "TXD0_35") (pintype "passive"))
    )
    (net (code "78") (name "Net-(U2-OSCI)") (class "Default")
      (node (ref "U2") (pin "20") (pinfunction "OSCI_20") (pintype "passive"))
      (node (ref "X1") (pin "2") (pinfunction "2_2") (pintype "passive"))
    )
    (net (code "79") (name "Net-(U2-OSCO)") (class "Default")
      (node (ref "U2") (pin "21") (pinfunction "OSCO_21") (pintype "passive"))
      (node (ref "X1") (pin "1") (pinfunction "1_1") (pintype "passive"))
    )
    (net (code "80") (name "Net-(U2-RESET#)") (class "Default")
      (node (ref "C7") (pin "2") (pinfunction "2_2") (pintype "passive"))
      (node (ref "R7") (pin "2") (pinfunction "2_2") (pintype "passive"))
      (node (ref "U2") (pin "41") (pinfunction "RESET#_41") (pintype "passive"))
    )
    (net (code "81") (name "Net-(U2-Vref)") (class "Default")
      (node (ref "C10") (pin "2") (pinfunction "2_2") (pintype "passive"))
      (node (ref "C9") (pin "2") (pinfunction "2_2") (pintype "passive"))
      (node (ref "U2") (pin "11") (pinfunction "Vref_11") (pintype "passive"))
    )
    (net (code "82") (name "unconnected-(U1-CLK-Pad20)") (class "Default")
      (node (ref "U1") (pin "20") (pinfunction "CLK_20") (pintype "passive+no_connect"))
    )
    (net (code "83") (name "unconnected-(U1-CMD-Pad19)") (class "Default")
      (node (ref "U1") (pin "19") (pinfunction "CMD_19") (pintype "passive+no_connect"))
    )
    (net (code "84") (name "unconnected-(U1-IO12-Pad14)") (class "Default")
      (node (ref "U1") (pin "14") (pinfunction "IO12_14") (pintype "passive+no_connect"))
    )
    (net (code "85") (name "unconnected-(U1-IO35-Pad7)") (class "Default")
      (node (ref "U1") (pin "7") (pinfunction "IO35_7") (pintype "passive+no_connect"))
    )
    (net (code "86") (name "unconnected-(U1-NC-Pad32)") (class "Default")
      (node (ref "U1") (pin "32") (pinfunction "NC_32") (pintype "passive+no_connect"))
    )
    (net (code "87") (name "unconnected-(U1-SD0-Pad21)") (class "Default")
      (node (ref "U1") (pin "21") (pinfunction "SD0_21") (pintype "passive+no_connect"))
    )
    (net (code "88") (name "unconnected-(U1-SD1-Pad22)") (class "Default")
      (node (ref "U1") (pin "22") (pinfunction "SD1_22") (pintype "passive+no_connect"))
    )
    (net (code "89") (name "unconnected-(U1-SD2-Pad17)") (class "Default")
      (node (ref "U1") (pin "17") (pinfunction "SD2_17") (pintype "passive+no_connect"))
    )
    (net (code "90") (name "unconnected-(U1-SD3-Pad18)") (class "Default")
      (node (ref "U1") (pin "18") (pinfunction "SD3_18") (pintype "passive+no_connect"))
    )
    (net (code "91") (name "unconnected-(U1-SENSOR_VN-Pad5)") (class "Default")
      (node (ref "U1") (pin "5") (pinfunction "SENSOR_VN_5") (pintype "passive+no_connect"))
    )
    (net (code "92") (name "unconnected-(U1-SENSOR_VP-Pad4)") (class "Default")
      (node (ref "U1") (pin "4") (pinfunction "SENSOR_VP_4") (pintype "passive+no_connect"))
    )
    (net (code "93") (name "unconnected-(U2-IRQ0-Pad30)") (class "Default")
      (node (ref "U2") (pin "30") (pinfunction "IRQ0_30") (pintype "passive+no_connect"))
    )
    (net (code "94") (name "unconnected-(U2-IRQ1-Pad31)") (class "Default")
      (node (ref "U2") (pin "31") (pinfunction "IRQ1_31") (pintype "passive+no_connect"))
    )
    (net (code "95") (name "unconnected-(U2-NC-Pad35)") (class "Default")
      (node (ref "U2") (pin "35") (pinfunction "NC_35") (pintype "passive+no_connect"))
    )
    (net (code "96") (name "unconnected-(U2-NC-Pad45)") (class "Default")
      (node (ref "U2") (pin "45") (pinfunction "NC_45") (pintype "passive+no_connect"))
    )
    (net (code "97") (name "unconnected-(U2-NC-Pad46)") (class "Default")
      (node (ref "U2") (pin "46") (pinfunction "NC_46") (pintype "passive+no_connect"))
    )
  )
)
